# LightBracelet_v0_1_0.net
KiCad netlist of a schematic drawn in EAGLE
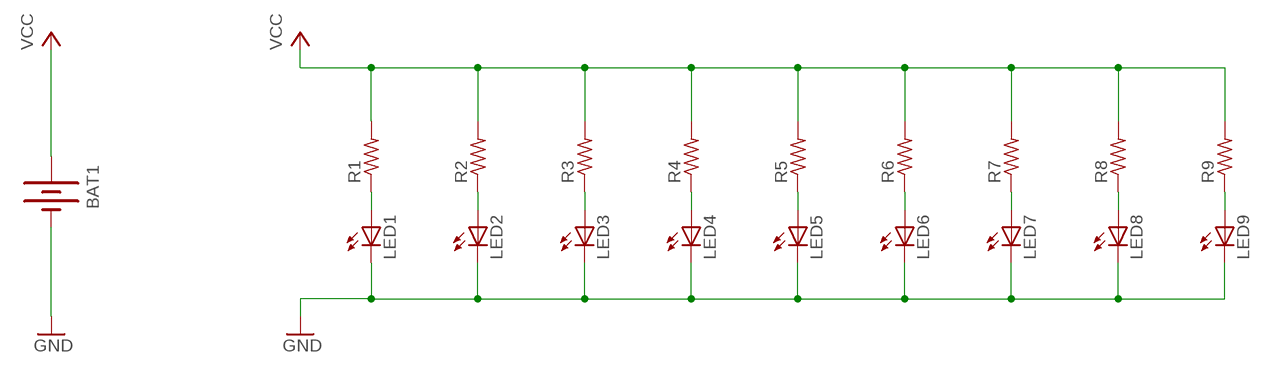
[diagram p0: schematic, sheet 1]

(export (version "E")
  (design (tool "Eeschema 10.0.6"))
  (components
    (comp (ref "BAT1")
      (value "BATTERY245MM")
      (footprint "eagle-import:BATTCON_245MM")
      (libsource (lib "eagle-import") (part "BATTERY245MM"))
    )
    (comp (ref "LED1")
      (value "LEDCHIPLED_1206")
      (footprint "eagle-import:CHIPLED_1206")
      (libsource (lib "eagle-import") (part "LEDCHIPLED_1206"))
    )
    (comp (ref "LED2")
      (value "LEDCHIPLED_1206")
      (footprint "eagle-import:CHIPLED_1206")
      (libsource (lib "eagle-import") (part "LEDCHIPLED_1206"))
    )
    (comp (ref "LED3")
      (value "LEDCHIPLED_1206")
      (footprint "eagle-import:CHIPLED_1206")
      (libsource (lib "eagle-import") (part "LEDCHIPLED_1206"))
    )
    (comp (ref "LED4")
      (value "LEDCHIPLED_1206")
      (footprint "eagle-import:CHIPLED_1206")
      (libsource (lib "eagle-import") (part "LEDCHIPLED_1206"))
    )
    (comp (ref "LED5")
      (value "LEDCHIPLED_1206")
      (footprint "eagle-import:CHIPLED_1206")
      (libsource (lib "eagle-import") (part "LEDCHIPLED_1206"))
    )
    (comp (ref "LED6")
      (value "LEDCHIPLED_1206")
      (footprint "eagle-import:CHIPLED_1206")
      (libsource (lib "eagle-import") (part "LEDCHIPLED_1206"))
    )
    (comp (ref "LED7")
      (value "LEDCHIPLED_1206")
      (footprint "eagle-import:CHIPLED_1206")
      (libsource (lib "eagle-import") (part "LEDCHIPLED_1206"))
    )
    (comp (ref "LED8")
      (value "LEDCHIPLED_1206")
      (footprint "eagle-import:CHIPLED_1206")
      (libsource (lib "eagle-import") (part "LEDCHIPLED_1206"))
    )
    (comp (ref "LED9")
      (value "LEDCHIPLED_1206")
      (footprint "eagle-import:CHIPLED_1206")
      (libsource (lib "eagle-import") (part "LEDCHIPLED_1206"))
    )
    (comp (ref "R1")
      (value "R-US_M0805")
      (footprint "eagle-import:M0805")
      (libsource (lib "eagle-import") (part "R-US_M0805"))
    )
    (comp (ref "R2")
      (value "R-US_M0805")
      (footprint "eagle-import:M0805")
      (libsource (lib "eagle-import") (part "R-US_M0805"))
    )
    (comp (ref "R3")
      (value "R-US_M0805")
      (footprint "eagle-import:M0805")
      (libsource (lib "eagle-import") (part "R-US_M0805"))
    )
    (comp (ref "R4")
      (value "R-US_M0805")
      (footprint "eagle-import:M0805")
      (libsource (lib "eagle-import") (part "R-US_M0805"))
    )
    (comp (ref "R5")
      (value "R-US_M0805")
      (footprint "eagle-import:M0805")
      (libsource (lib "eagle-import") (part "R-US_M0805"))
    )
    (comp (ref "R6")
      (value "R-US_M0805")
      (footprint "eagle-import:M0805")
      (libsource (lib "eagle-import") (part "R-US_M0805"))
    )
    (comp (ref "R7")
      (value "R-US_M0805")
      (footprint "eagle-import:M0805")
      (libsource (lib "eagle-import") (part "R-US_M0805"))
    )
    (comp (ref "R8")
      (value "R-US_M0805")
      (footprint "eagle-import:M0805")
      (libsource (lib "eagle-import") (part "R-US_M0805"))
    )
    (comp (ref "R9")
      (value "R-US_M0805")
      (footprint "eagle-import:M0805")
      (libsource (lib "eagle-import") (part "R-US_M0805"))
    )
  )
  (nets
    (net (code "1") (name "GND") (class "Default")
      (node (ref "BAT1") (pin "2") (pinfunction "-_2") (pintype "power_in"))
      (node (ref "LED1") (pin "C") (pinfunction "C_C") (pintype "passive"))
      (node (ref "LED2") (pin "C") (pinfunction "C_C") (pintype "passive"))
      (node (ref "LED3") (pin "C") (pinfunction "C_C") (pintype "passive"))
      (node (ref "LED4") (pin "C") (pinfunction "C_C") (pintype "passive"))
      (node (ref "LED5") (pin "C") (pinfunction "C_C") (pintype "passive"))
      (node (ref "LED6") (pin "C") (pinfunction "C_C") (pintype "passive"))
      (node (ref "LED7") (pin "C") (pinfunction "C_C") (pintype "passive"))
      (node (ref "LED8") (pin "C") (pinfunction "C_C") (pintype "passive"))
      (node (ref "LED9") (pin "C") (pinfunction "C_C") (pintype "passive"))
    )
    (net (code "2") (name "Net-(LED1-PadA)") (class "Default")
      (node (ref "LED1") (pin "A") (pinfunction "A_A") (pintype "passive"))
      (node (ref "R1") (pin "1") (pinfunction "1_1") (pintype "passive"))
    )
    (net (code "3") (name "Net-(LED2-PadA)") (class "Default")
      (node (ref "LED2") (pin "A") (pinfunction "A_A") (pintype "passive"))
      (node (ref "R2") (pin "1") (pinfunction "1_1") (pintype "passive"))
    )
    (net (code "4") (name "Net-(LED3-PadA)") (class "Default")
      (node (ref "LED3") (pin "A") (pinfunction "A_A") (pintype "passive"))
      (node (ref "R3") (pin "1") (pinfunction "1_1") (pintype "passive"))
    )
    (net (code "5") (name "Net-(LED4-PadA)") (class "Default")
      (node (ref "LED4") (pin "A") (pinfunction "A_A") (pintype "passive"))
      (node (ref "R4") (pin "1") (pinfunction "1_1") (pintype "passive"))
    )
    (net (code "6") (name "Net-(LED5-PadA)") (class "Default")
      (node (ref "LED5") (pin "A") (pinfunction "A_A") (pintype "passive"))
      (node (ref "R5") (pin "1") (pinfunction "1_1") (pintype "passive"))
    )
    (net (code "7") (name "Net-(LED6-PadA)") (class "Default")
      (node (ref "LED6") (pin "A") (pinfunction "A_A") (pintype "passive"))
      (node (ref "R6") (pin "1") (pinfunction "1_1") (pintype "passive"))
    )
    (net (code "8") (name "Net-(LED7-PadA)") (class "Default")
      (node (ref "LED7") (pin "A") (pinfunction "A_A") (pintype "passive"))
      (node (ref "R7") (pin "1") (pinfunction "1_1") (pintype "passive"))
    )
    (net (code "9") (name "Net-(LED8-PadA)") (class "Default")
      (node (ref "LED8") (pin "A") (pinfunction "A_A") (pintype "passive"))
      (node (ref "R8") (pin "1") (pinfunction "1_1") (pintype "passive"))
    )
    (net (code "10") (name "Net-(LED9-PadA)") (class "Default")
      (node (ref "LED9") (pin "A") (pinfunction "A_A") (pintype "passive"))
      (node (ref "R9") (pin "1") (pinfunction "1_1") (pintype "passive"))
    )
    (net (code "11") (name "VCC") (class "Default")
      (node (ref "BAT1") (pin "1") (pinfunction "+_1") (pintype "power_in"))
      (node (ref "R1") (pin "2") (pinfunction "2_2") (pintype "passive"))
      (node (ref "R2") (pin "2") (pinfunction "2_2") (pintype "passive"))
      (node (ref "R3") (pin "2") (pinfunction "2_2") (pintype "passive"))
      (node (ref "R4") (pin "2") (pinfunction "2_2") (pintype "passive"))
      (node (ref "R5") (pin "2") (pinfunction "2_2") (pintype "passive"))
      (node (ref "R6") (pin "2") (pinfunction "2_2") (pintype "passive"))
      (node (ref "R7") (pin "2") (pinfunction "2_2") (pintype "passive"))
      (node (ref "R8") (pin "2") (pinfunction "2_2") (pintype "passive"))
      (node (ref "R9") (pin "2") (pinfunction "2_2") (pintype "passive"))
    )
  )
)
